# LIC_rack_BB-00.net
KiCad netlist of a schematic drawn in EAGLE
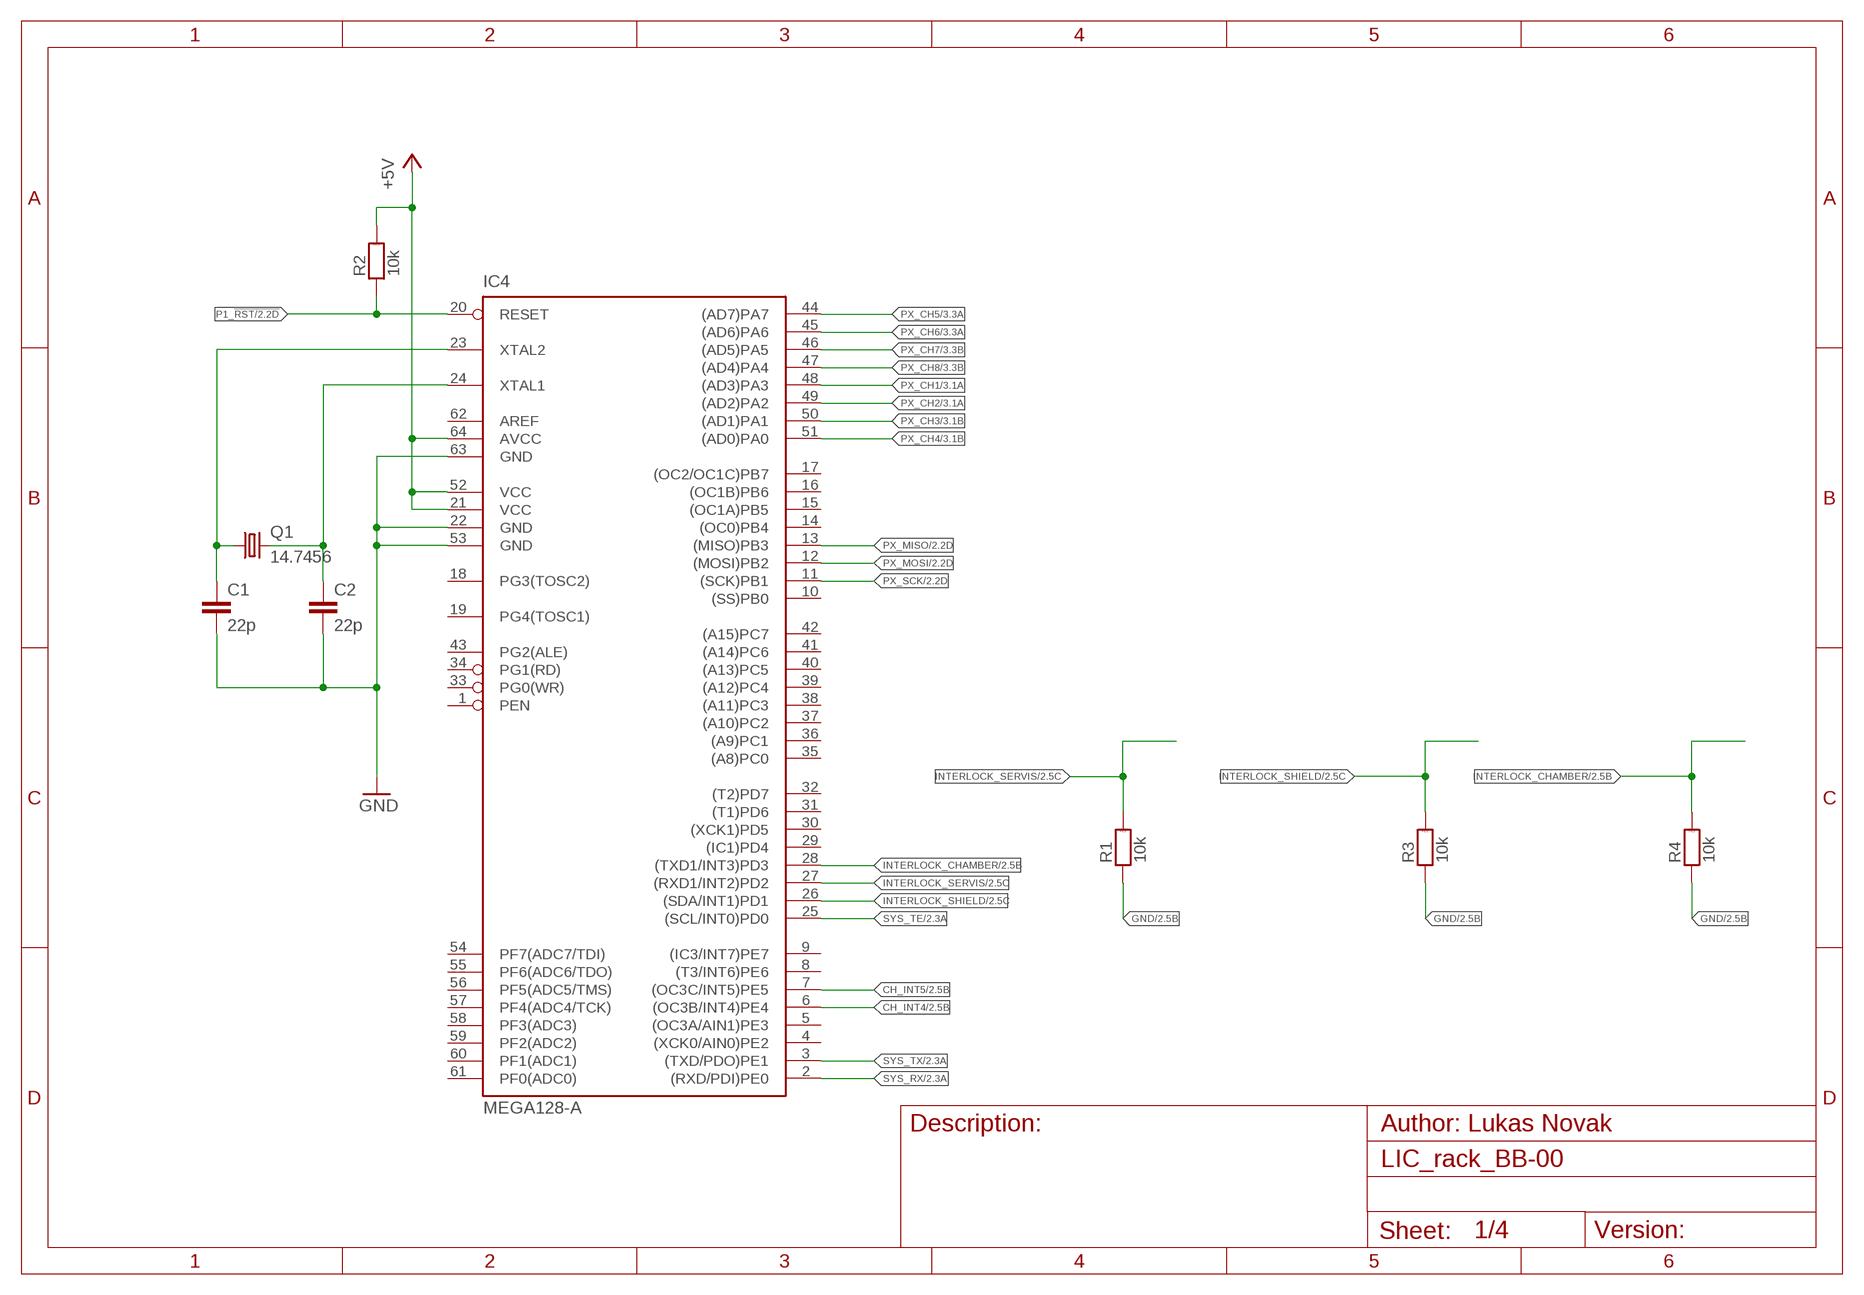
[diagram p0: schematic, sheet 1]
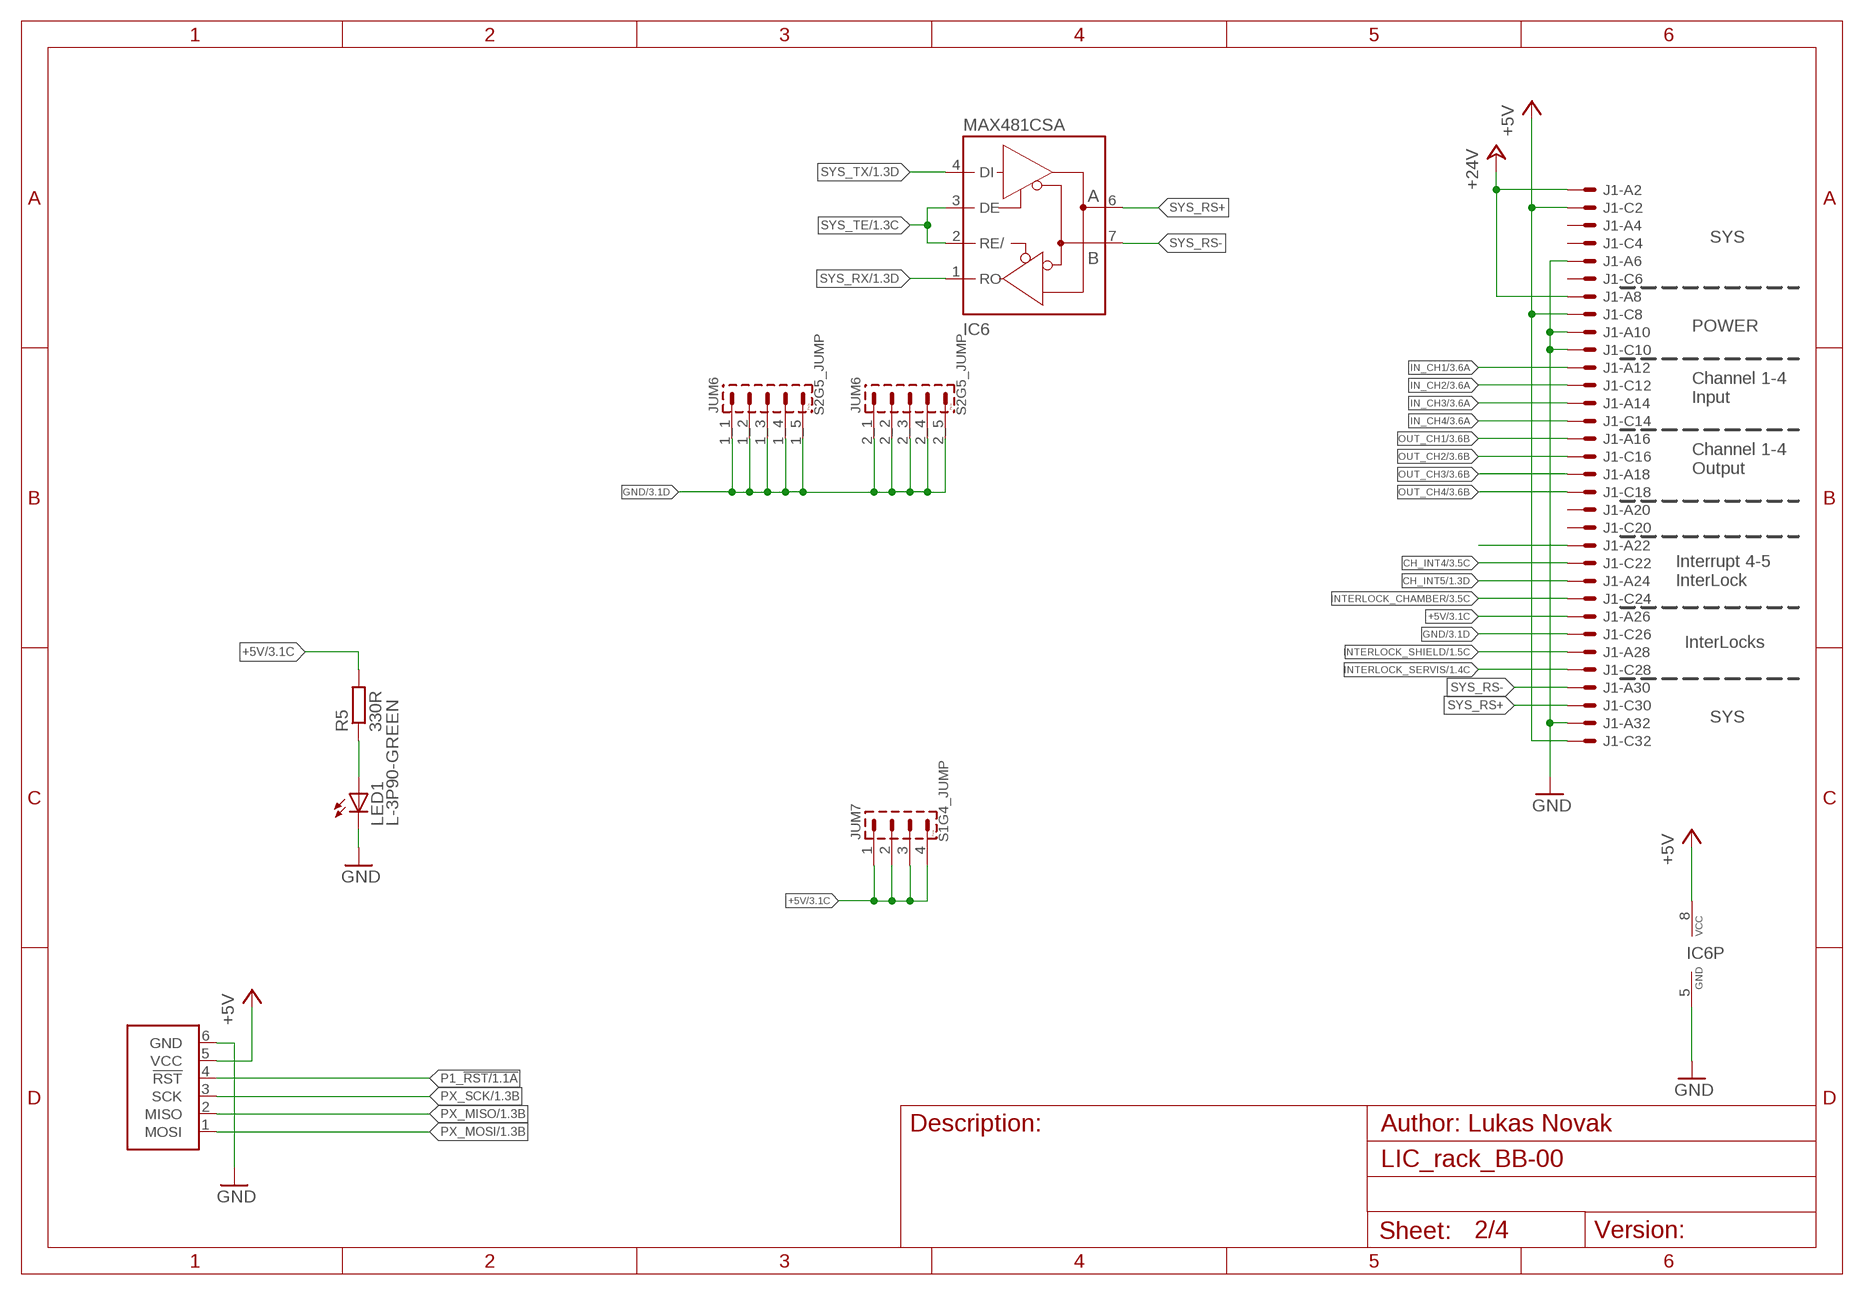
[diagram p1: schematic, sheet 2]
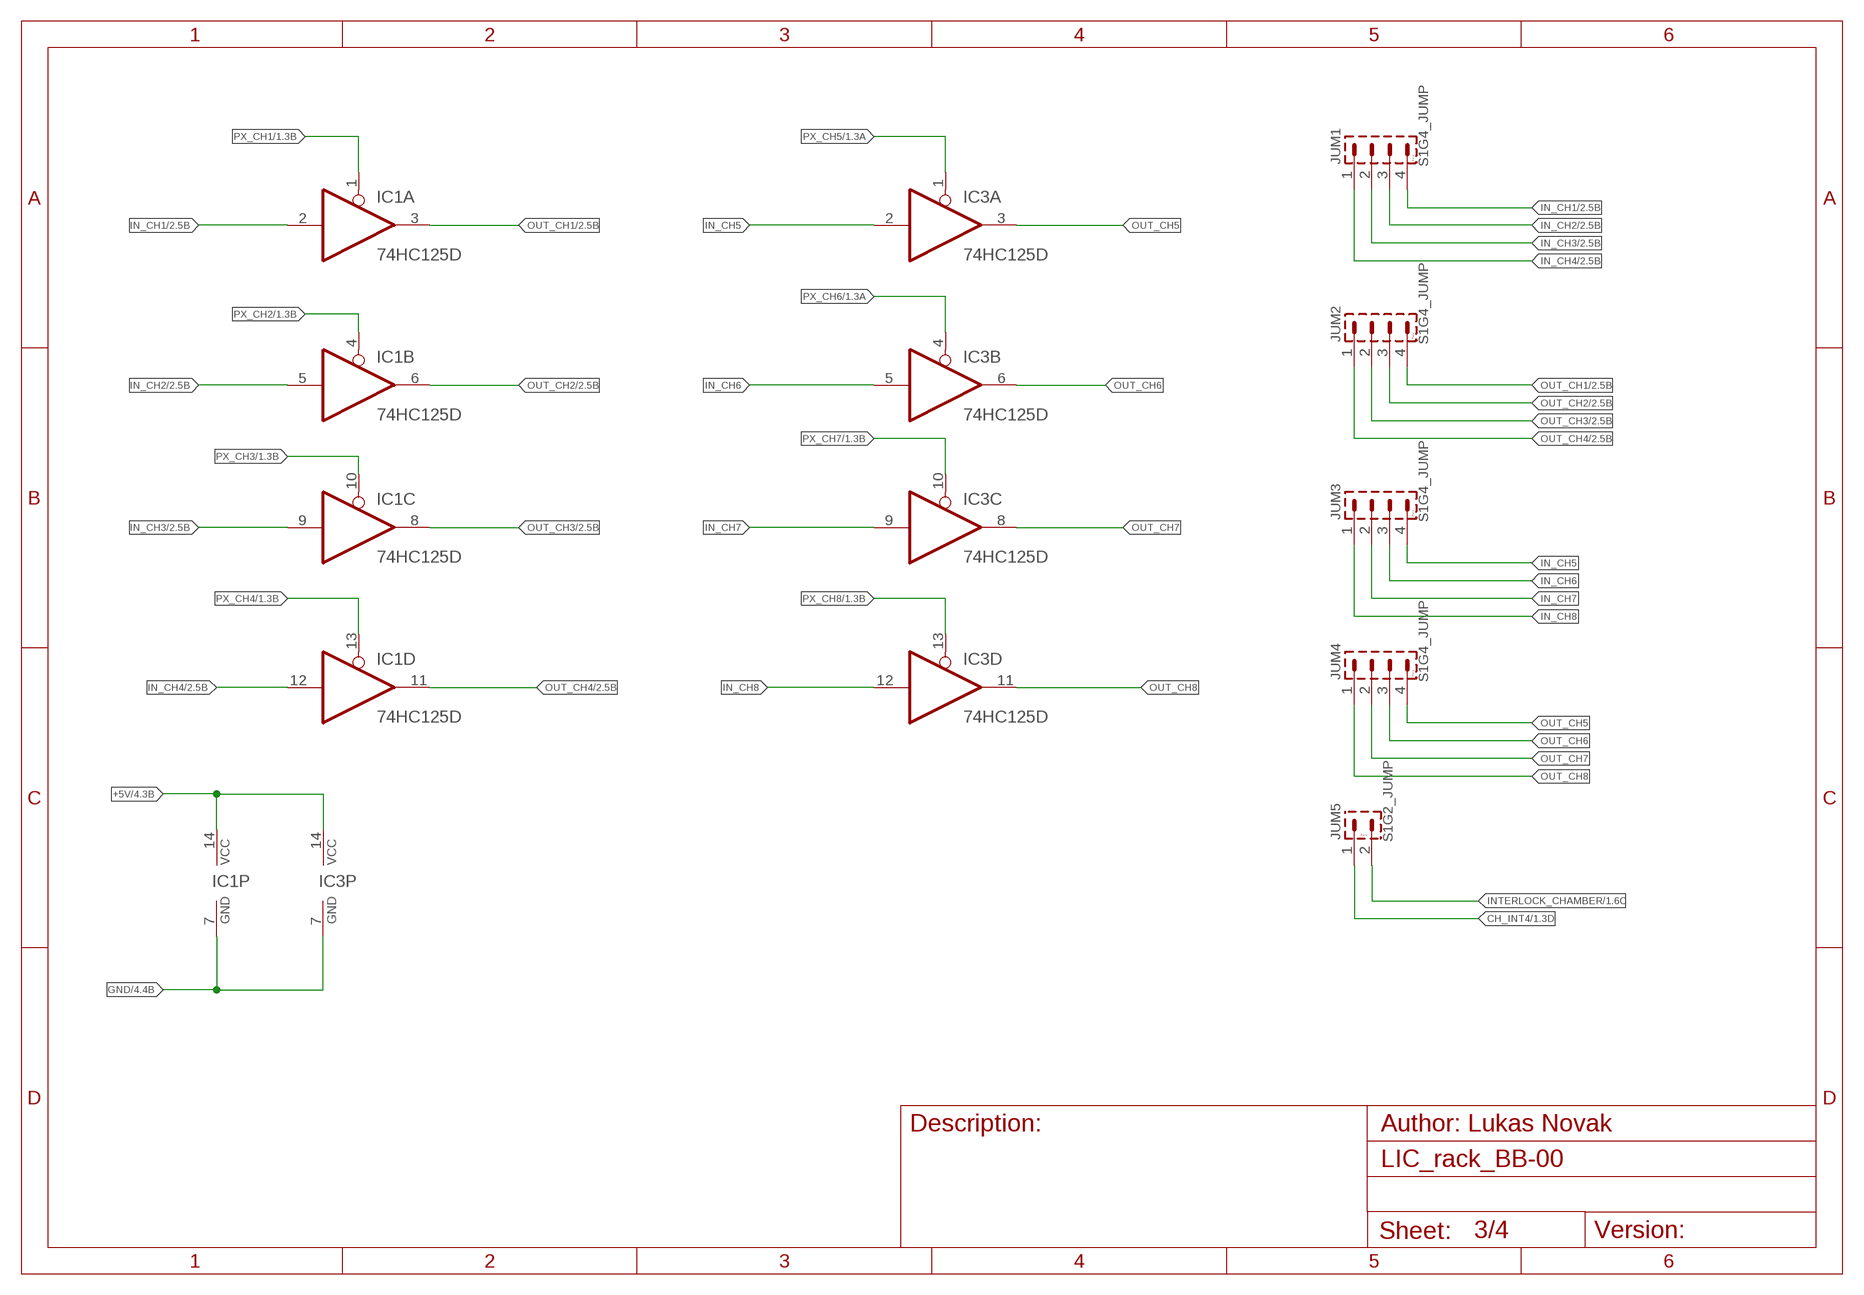
[diagram p2: schematic, sheet 3]
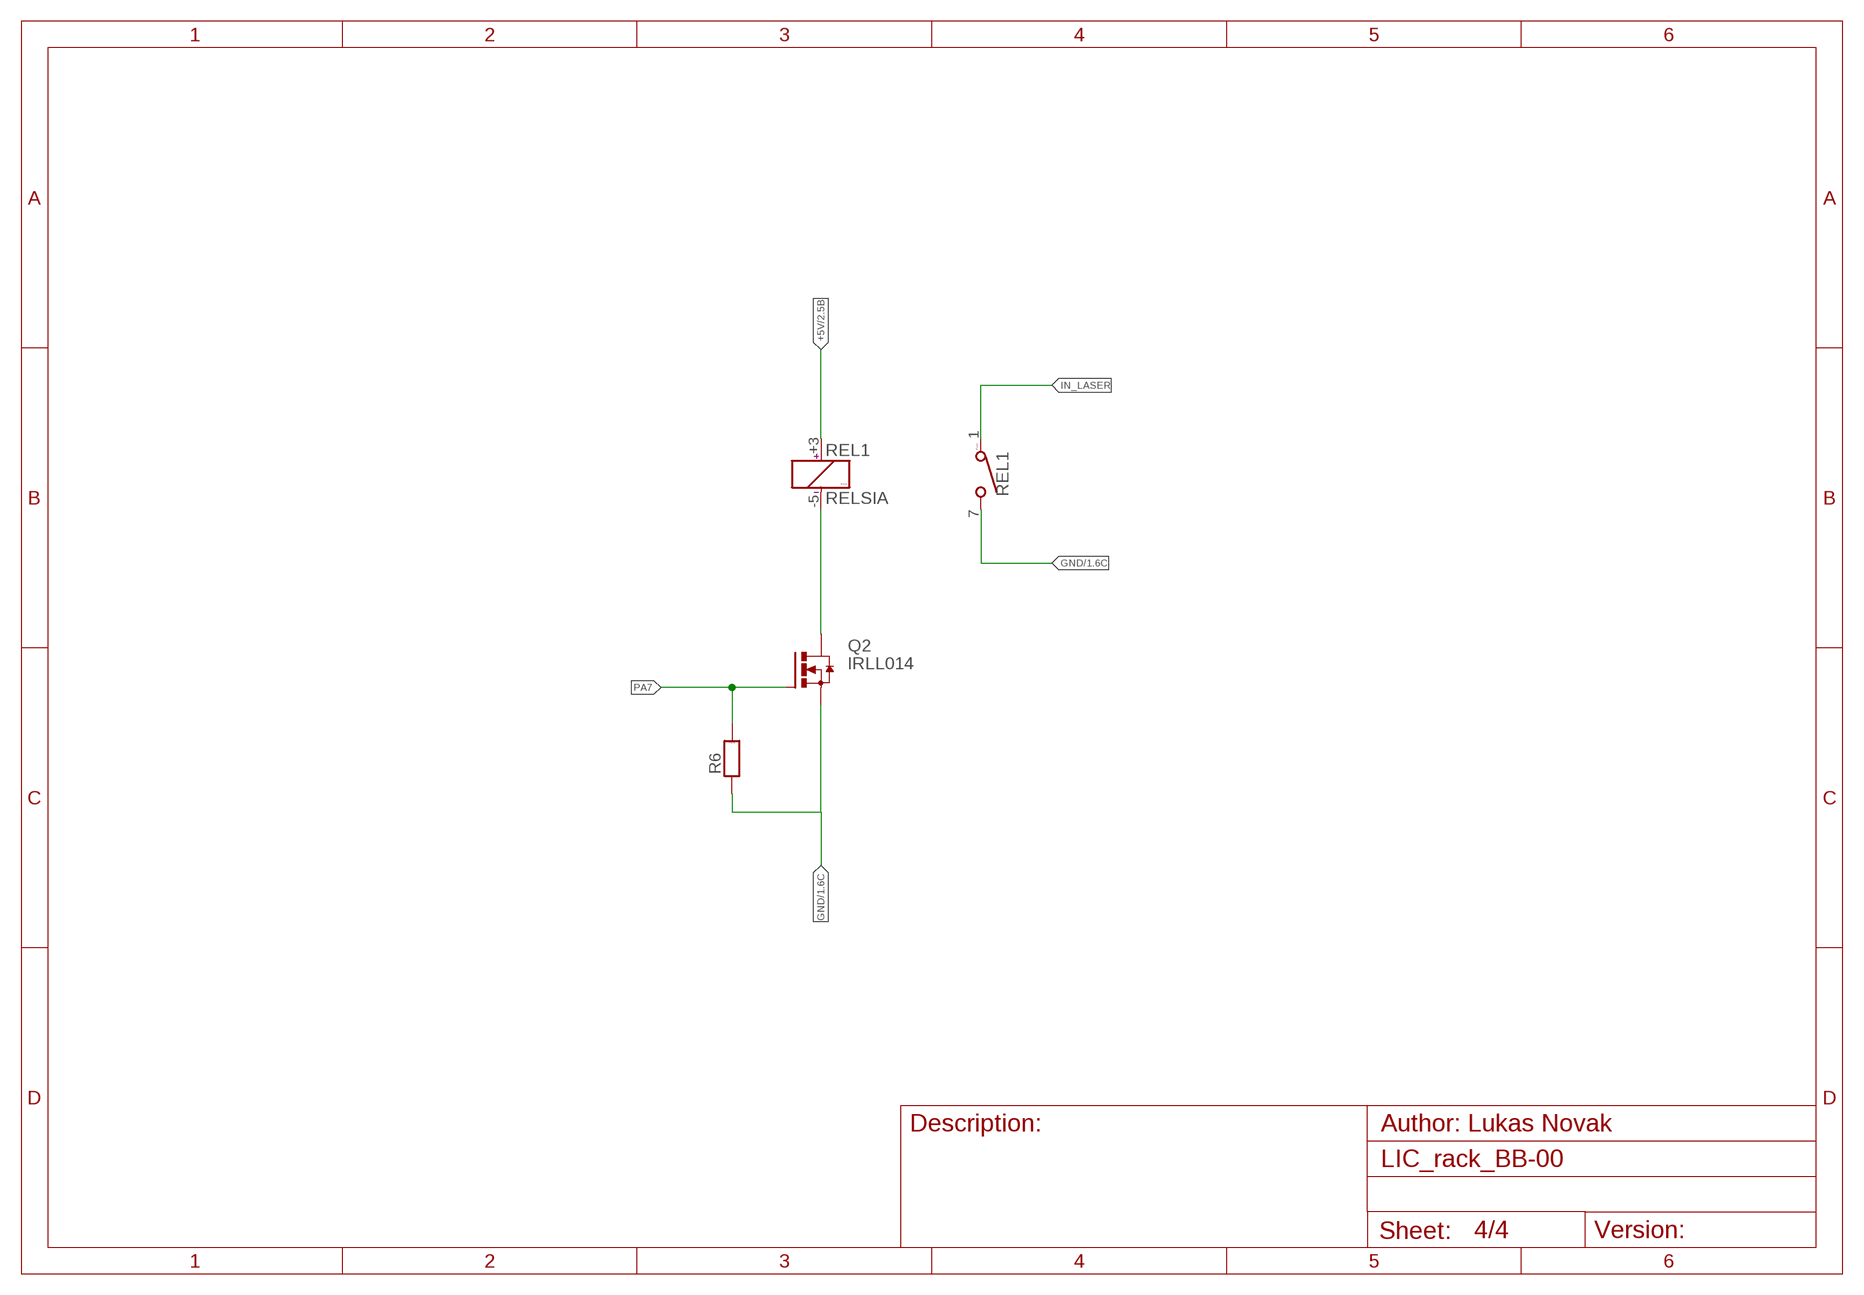
[diagram p3: schematic, sheet 4]

(export (version "E")
  (design (tool "Eeschema 10.0.6"))
  (components
    (comp (ref "C1")
      (value "22p")
      (footprint "eagle-import:C0805")
      (libsource (lib "eagle-import") (part "C-EUC0805"))
    )
    (comp (ref "C2")
      (value "22p")
      (footprint "eagle-import:C0805")
      (libsource (lib "eagle-import") (part "C-EUC0805"))
    )
    (comp (ref "IC4")
      (value "MEGA128-A")
      (footprint "eagle-import:TQFP64")
      (fields (field (name "MPN") "ATMEGA128-16AU"))
      (libsource (lib "eagle-import") (part "MEGA128-A"))
    )
    (comp (ref "Q1")
      (value "14.7456")
      (footprint "eagle-import:HC49U70")
      (libsource (lib "eagle-import") (part "XTAL"))
    )
    (comp (ref "R1")
      (value "10k")
      (footprint "eagle-import:1206")
      (libsource (lib "eagle-import") (part "R_1206"))
    )
    (comp (ref "R2")
      (value "10k")
      (footprint "eagle-import:1206")
      (libsource (lib "eagle-import") (part "R_1206"))
    )
    (comp (ref "R3")
      (value "10k")
      (footprint "eagle-import:1206")
      (libsource (lib "eagle-import") (part "R_1206"))
    )
    (comp (ref "R4")
      (value "10k")
      (footprint "eagle-import:1206")
      (libsource (lib "eagle-import") (part "R_1206"))
    )
    (comp (ref "IC1")
      (value "74HC125D")
      (footprint "eagle-import:SO14")
      (libsource (lib "eagle-import") (part "74125DHC"))
    )
    (comp (ref "IC3")
      (value "74HC125D")
      (footprint "eagle-import:SO14")
      (libsource (lib "eagle-import") (part "74125DHC"))
    )
    (comp (ref "JUM1")
      (value "S1G4_JUMP")
      (footprint "eagle-import:S1G4_JUM")
      (libsource (lib "eagle-import") (part "S1G4_JUMP"))
    )
    (comp (ref "JUM2")
      (value "S1G4_JUMP")
      (footprint "eagle-import:S1G4_JUM")
      (libsource (lib "eagle-import") (part "S1G4_JUMP"))
    )
    (comp (ref "JUM3")
      (value "S1G4_JUMP")
      (footprint "eagle-import:S1G4_JUM")
      (libsource (lib "eagle-import") (part "S1G4_JUMP"))
    )
    (comp (ref "JUM4")
      (value "S1G4_JUMP")
      (footprint "eagle-import:S1G4_JUM")
      (libsource (lib "eagle-import") (part "S1G4_JUMP"))
    )
    (comp (ref "JUM5")
      (value "S1G2_JUMP")
      (footprint "eagle-import:S1G2_JUM")
      (libsource (lib "eagle-import") (part "S1G2_JUMP"))
    )
    (comp (ref "IC6")
      (value "MAX481CSA")
      (footprint "eagle-import:SO08")
      (libsource (lib "eagle-import") (part "MAX481CSA"))
    )
    (comp (ref "J1")
      (value "VG32SP")
      (footprint "eagle-import:VG32P")
      (libsource (lib "eagle-import") (part "VG32SP"))
    )
    (comp (ref "JUM6")
      (value "S2G5_JUMP")
      (footprint "eagle-import:S2G5_JUM")
      (libsource (lib "eagle-import") (part "S2G5_JUMP"))
    )
    (comp (ref "JUM7")
      (value "S1G4_JUMP")
      (footprint "eagle-import:S1G4_JUM")
      (libsource (lib "eagle-import") (part "S1G4_JUMP"))
    )
    (comp (ref "LED1")
      (value "L-3P90-GREEN")
      (footprint "eagle-import:L-3P90")
      (libsource (lib "eagle-import") (part "L-3P90-GREEN"))
    )
    (comp (ref "R5")
      (value "330R")
      (footprint "eagle-import:R1206")
      (libsource (lib "eagle-import") (part "R-EU_R1206"))
    )
    (comp (ref "U1")
      (value "ATPROG-V")
      (footprint "eagle-import:6410-06")
      (libsource (lib "eagle-import") (part "ATPROG-V"))
    )
    (comp (ref "Q2")
      (value "IRLL014")
      (footprint "eagle-import:SOT223")
      (libsource (lib "eagle-import") (part "N-HEXFET-2D_?-SOT232"))
    )
    (comp (ref "R6")
      (value "R_1206")
      (footprint "eagle-import:1206")
      (libsource (lib "eagle-import") (part "R_1206"))
    )
    (comp (ref "REL1")
      (value "RELSIA")
      (footprint "eagle-import:RELSIA")
      (libsource (lib "eagle-import") (part "RELSIA??"))
    )
  )
  (nets
    (net (code "1") (name "+5V") (class "Default")
      (node (ref "IC1") (pin "14") (pinfunction "VCC_14") (pintype "power_in"))
      (node (ref "IC3") (pin "14") (pinfunction "VCC_14") (pintype "power_in"))
      (node (ref "IC4") (pin "21") (pinfunction "VCC_21") (pintype "power_in"))
      (node (ref "IC4") (pin "52") (pinfunction "VCC_52") (pintype "power_in"))
      (node (ref "IC4") (pin "64") (pinfunction "AVCC_64") (pintype "power_in"))
      (node (ref "IC6") (pin "8") (pinfunction "VCC_8") (pintype "power_in"))
      (node (ref "J1") (pin "A26") (pinfunction "MS_A26") (pintype "passive"))
      (node (ref "J1") (pin "C2") (pinfunction "MS_C2") (pintype "passive"))
      (node (ref "J1") (pin "C32") (pinfunction "MSV_C32") (pintype "passive"))
      (node (ref "J1") (pin "C8") (pinfunction "MS_C8") (pintype "passive"))
      (node (ref "JUM7") (pin "1") (pinfunction "1_1") (pintype "passive"))
      (node (ref "JUM7") (pin "2") (pinfunction "2_2") (pintype "passive"))
      (node (ref "JUM7") (pin "3") (pinfunction "3_3") (pintype "passive"))
      (node (ref "JUM7") (pin "4") (pinfunction "4_4") (pintype "passive"))
      (node (ref "R2") (pin "2") (pinfunction "2_2") (pintype "passive"))
      (node (ref "R5") (pin "2") (pinfunction "2_2") (pintype "passive"))
      (node (ref "REL1") (pin "+3") (pinfunction "C+_+3") (pintype "passive"))
      (node (ref "U1") (pin "5") (pinfunction "VCC_5") (pintype "power_in"))
    )
    (net (code "2") (name "+24V") (class "Default")
      (node (ref "J1") (pin "A2") (pinfunction "MS_A2") (pintype "passive"))
      (node (ref "J1") (pin "A8") (pinfunction "MS_A8") (pintype "passive"))
    )
    (net (code "3") (name "CH_INT4") (class "Default")
      (node (ref "IC4") (pin "6") (pinfunction "(OC3B/INT4)PE4_6") (pintype "bidirectional"))
      (node (ref "J1") (pin "C22") (pinfunction "MS_C22") (pintype "passive"))
      (node (ref "JUM5") (pin "1") (pinfunction "1_1") (pintype "passive"))
    )
    (net (code "4") (name "CH_INT5") (class "Default")
      (node (ref "IC4") (pin "7") (pinfunction "(OC3C/INT5)PE5_7") (pintype "bidirectional"))
      (node (ref "J1") (pin "A24") (pinfunction "MS_A24") (pintype "passive"))
    )
    (net (code "5") (name "GND") (class "Default")
      (node (ref "C1") (pin "2") (pinfunction "2_2") (pintype "passive"))
      (node (ref "C2") (pin "2") (pinfunction "2_2") (pintype "passive"))
      (node (ref "IC1") (pin "7") (pinfunction "GND_7") (pintype "power_in"))
      (node (ref "IC3") (pin "7") (pinfunction "GND_7") (pintype "power_in"))
      (node (ref "IC4") (pin "22") (pinfunction "GND_22") (pintype "power_in"))
      (node (ref "IC4") (pin "53") (pinfunction "GND_53") (pintype "power_in"))
      (node (ref "IC4") (pin "63") (pinfunction "GND_63") (pintype "power_in"))
      (node (ref "IC6") (pin "5") (pinfunction "GND_5") (pintype "power_in"))
      (node (ref "J1") (pin "A10") (pinfunction "MS_A10") (pintype "passive"))
      (node (ref "J1") (pin "A32") (pinfunction "MS_A32") (pintype "passive"))
      (node (ref "J1") (pin "A6") (pinfunction "MS_A6") (pintype "passive"))
      (node (ref "J1") (pin "C10") (pinfunction "MS_C10") (pintype "passive"))
      (node (ref "J1") (pin "C26") (pinfunction "MS_C26") (pintype "passive"))
      (node (ref "JUM6") (pin "1_1") (pinfunction "1_1_1") (pintype "passive"))
      (node (ref "JUM6") (pin "1_2") (pinfunction "2_1_2") (pintype "passive"))
      (node (ref "JUM6") (pin "1_3") (pinfunction "3_1_3") (pintype "passive"))
      (node (ref "JUM6") (pin "1_4") (pinfunction "4_1_4") (pintype "passive"))
      (node (ref "JUM6") (pin "1_5") (pinfunction "5_1_5") (pintype "passive"))
      (node (ref "JUM6") (pin "2_1") (pinfunction "1_2_1") (pintype "passive"))
      (node (ref "JUM6") (pin "2_2") (pinfunction "2_2_2") (pintype "passive"))
      (node (ref "JUM6") (pin "2_3") (pinfunction "3_2_3") (pintype "passive"))
      (node (ref "JUM6") (pin "2_4") (pinfunction "4_2_4") (pintype "passive"))
      (node (ref "JUM6") (pin "2_5") (pinfunction "5_2_5") (pintype "passive"))
      (node (ref "LED1") (pin "K") (pinfunction "C_K") (pintype "passive"))
      (node (ref "Q2") (pin "3") (pinfunction "S_3") (pintype "passive"))
      (node (ref "R1") (pin "1") (pinfunction "1_1") (pintype "passive"))
      (node (ref "R3") (pin "1") (pinfunction "1_1") (pintype "passive"))
      (node (ref "R4") (pin "1") (pinfunction "1_1") (pintype "passive"))
      (node (ref "R6") (pin "1") (pinfunction "1_1") (pintype "passive"))
      (node (ref "REL1") (pin "7") (pinfunction "2_7") (pintype "passive"))
      (node (ref "U1") (pin "6") (pinfunction "GND_6") (pintype "power_in"))
    )
    (net (code "6") (name "INTERLOCK_CHAMBER") (class "Default")
      (node (ref "IC4") (pin "28") (pinfunction "(TXD1/INT3)PD3_28") (pintype "bidirectional"))
      (node (ref "J1") (pin "C24") (pinfunction "MS_C24") (pintype "passive"))
      (node (ref "JUM5") (pin "2") (pinfunction "2_2") (pintype "passive"))
      (node (ref "R4") (pin "2") (pinfunction "2_2") (pintype "passive"))
    )
    (net (code "7") (name "INTERLOCK_SERVIS") (class "Default")
      (node (ref "IC4") (pin "27") (pinfunction "(RXD1/INT2)PD2_27") (pintype "bidirectional"))
      (node (ref "J1") (pin "C28") (pinfunction "MS_C28") (pintype "passive"))
      (node (ref "R1") (pin "2") (pinfunction "2_2") (pintype "passive"))
    )
    (net (code "8") (name "INTERLOCK_SHIELD") (class "Default")
      (node (ref "IC4") (pin "26") (pinfunction "(SDA/INT1)PD1_26") (pintype "bidirectional"))
      (node (ref "J1") (pin "A28") (pinfunction "MS_A28") (pintype "passive"))
      (node (ref "R3") (pin "2") (pinfunction "2_2") (pintype "passive"))
    )
    (net (code "9") (name "IN_CH1") (class "Default")
      (node (ref "IC1") (pin "2") (pinfunction "I_2") (pintype "input"))
      (node (ref "J1") (pin "A12") (pinfunction "MS_A12") (pintype "passive"))
      (node (ref "JUM1") (pin "4") (pinfunction "4_4") (pintype "passive"))
    )
    (net (code "10") (name "IN_CH2") (class "Default")
      (node (ref "IC1") (pin "5") (pinfunction "I_5") (pintype "input"))
      (node (ref "J1") (pin "C12") (pinfunction "MS_C12") (pintype "passive"))
      (node (ref "JUM1") (pin "3") (pinfunction "3_3") (pintype "passive"))
    )
    (net (code "11") (name "IN_CH3") (class "Default")
      (node (ref "IC1") (pin "9") (pinfunction "I_9") (pintype "input"))
      (node (ref "J1") (pin "A14") (pinfunction "MS_A14") (pintype "passive"))
      (node (ref "JUM1") (pin "2") (pinfunction "2_2") (pintype "passive"))
    )
    (net (code "12") (name "IN_CH4") (class "Default")
      (node (ref "IC1") (pin "12") (pinfunction "I_12") (pintype "input"))
      (node (ref "J1") (pin "C14") (pinfunction "MS_C14") (pintype "passive"))
      (node (ref "JUM1") (pin "1") (pinfunction "1_1") (pintype "passive"))
    )
    (net (code "13") (name "IN_CH5") (class "Default")
      (node (ref "IC3") (pin "2") (pinfunction "I_2") (pintype "input"))
      (node (ref "JUM3") (pin "4") (pinfunction "4_4") (pintype "passive"))
    )
    (net (code "14") (name "IN_CH6") (class "Default")
      (node (ref "IC3") (pin "5") (pinfunction "I_5") (pintype "input"))
      (node (ref "JUM3") (pin "3") (pinfunction "3_3") (pintype "passive"))
    )
    (net (code "15") (name "IN_CH7") (class "Default")
      (node (ref "IC3") (pin "9") (pinfunction "I_9") (pintype "input"))
      (node (ref "JUM3") (pin "2") (pinfunction "2_2") (pintype "passive"))
    )
    (net (code "16") (name "IN_CH8") (class "Default")
      (node (ref "IC3") (pin "12") (pinfunction "I_12") (pintype "input"))
      (node (ref "JUM3") (pin "1") (pinfunction "1_1") (pintype "passive"))
    )
    (net (code "17") (name "IN_LASER") (class "Default")
      (node (ref "REL1") (pin "1") (pinfunction "1_1") (pintype "passive"))
    )
    (net (code "18") (name "Net-(IC4-XTAL1)") (class "Default")
      (node (ref "C2") (pin "1") (pinfunction "1_1") (pintype "passive"))
      (node (ref "IC4") (pin "24") (pinfunction "XTAL1_24") (pintype "bidirectional"))
      (node (ref "Q1") (pin "2") (pinfunction "2_2") (pintype "passive"))
    )
    (net (code "19") (name "Net-(IC4-XTAL2)") (class "Default")
      (node (ref "C1") (pin "1") (pinfunction "1_1") (pintype "passive"))
      (node (ref "IC4") (pin "23") (pinfunction "XTAL2_23") (pintype "bidirectional"))
      (node (ref "Q1") (pin "1") (pinfunction "1_1") (pintype "passive"))
    )
    (net (code "20") (name "Net-(LED1-PadA)") (class "Default")
      (node (ref "LED1") (pin "A") (pinfunction "A_A") (pintype "passive"))
      (node (ref "R5") (pin "1") (pinfunction "1_1") (pintype "passive"))
    )
    (net (code "21") (name "Net-(REL1A-C-)") (class "Default")
      (node (ref "Q2") (pin "2") (pinfunction "D_2") (pintype "passive"))
      (node (ref "Q2") (pin "4") (pinfunction "D_4") (pintype "passive"))
      (node (ref "REL1") (pin "-5") (pinfunction "C-_-5") (pintype "passive"))
    )
    (net (code "22") (name "OUT_CH1") (class "Default")
      (node (ref "IC1") (pin "3") (pinfunction "O_3") (pintype "tri_state"))
      (node (ref "J1") (pin "A16") (pinfunction "MS_A16") (pintype "passive"))
      (node (ref "JUM2") (pin "4") (pinfunction "4_4") (pintype "passive"))
    )
    (net (code "23") (name "OUT_CH2") (class "Default")
      (node (ref "IC1") (pin "6") (pinfunction "O_6") (pintype "tri_state"))
      (node (ref "J1") (pin "C16") (pinfunction "MS_C16") (pintype "passive"))
      (node (ref "JUM2") (pin "3") (pinfunction "3_3") (pintype "passive"))
    )
    (net (code "24") (name "OUT_CH3") (class "Default")
      (node (ref "IC1") (pin "8") (pinfunction "O_8") (pintype "tri_state"))
      (node (ref "J1") (pin "A18") (pinfunction "MS_A18") (pintype "passive"))
      (node (ref "JUM2") (pin "2") (pinfunction "2_2") (pintype "passive"))
    )
    (net (code "25") (name "OUT_CH4") (class "Default")
      (node (ref "IC1") (pin "11") (pinfunction "O_11") (pintype "tri_state"))
      (node (ref "J1") (pin "C18") (pinfunction "MS_C18") (pintype "passive"))
      (node (ref "JUM2") (pin "1") (pinfunction "1_1") (pintype "passive"))
    )
    (net (code "26") (name "OUT_CH5") (class "Default")
      (node (ref "IC3") (pin "3") (pinfunction "O_3") (pintype "tri_state"))
      (node (ref "JUM4") (pin "4") (pinfunction "4_4") (pintype "passive"))
    )
    (net (code "27") (name "OUT_CH6") (class "Default")
      (node (ref "IC3") (pin "6") (pinfunction "O_6") (pintype "tri_state"))
      (node (ref "JUM4") (pin "3") (pinfunction "3_3") (pintype "passive"))
    )
    (net (code "28") (name "OUT_CH7") (class "Default")
      (node (ref "IC3") (pin "8") (pinfunction "O_8") (pintype "tri_state"))
      (node (ref "JUM4") (pin "2") (pinfunction "2_2") (pintype "passive"))
    )
    (net (code "29") (name "OUT_CH8") (class "Default")
      (node (ref "IC3") (pin "11") (pinfunction "O_11") (pintype "tri_state"))
      (node (ref "JUM4") (pin "1") (pinfunction "1_1") (pintype "passive"))
    )
    (net (code "30") (name "P1_~{RST}") (class "Default")
      (node (ref "IC4") (pin "20") (pinfunction "RESET_20") (pintype "input"))
      (node (ref "R2") (pin "1") (pinfunction "1_1") (pintype "passive"))
      (node (ref "U1") (pin "4") (pinfunction "~{RST}_4") (pintype "input"))
    )
    (net (code "31") (name "PA7") (class "Default")
      (node (ref "Q2") (pin "1") (pinfunction "G_1") (pintype "passive"))
      (node (ref "R6") (pin "2") (pinfunction "2_2") (pintype "passive"))
    )
    (net (code "32") (name "PX_CH1") (class "Default")
      (node (ref "IC1") (pin "1") (pinfunction "OE_1") (pintype "input"))
      (node (ref "IC4") (pin "48") (pinfunction "(AD3)PA3_48") (pintype "bidirectional"))
    )
    (net (code "33") (name "PX_CH2") (class "Default")
      (node (ref "IC1") (pin "4") (pinfunction "OE_4") (pintype "input"))
      (node (ref "IC4") (pin "49") (pinfunction "(AD2)PA2_49") (pintype "bidirectional"))
    )
    (net (code "34") (name "PX_CH3") (class "Default")
      (node (ref "IC1") (pin "10") (pinfunction "OE_10") (pintype "input"))
      (node (ref "IC4") (pin "50") (pinfunction "(AD1)PA1_50") (pintype "bidirectional"))
    )
    (net (code "35") (name "PX_CH4") (class "Default")
      (node (ref "IC1") (pin "13") (pinfunction "OE_13") (pintype "input"))
      (node (ref "IC4") (pin "51") (pinfunction "(AD0)PA0_51") (pintype "bidirectional"))
    )
    (net (code "36") (name "PX_CH5") (class "Default")
      (node (ref "IC3") (pin "1") (pinfunction "OE_1") (pintype "input"))
      (node (ref "IC4") (pin "44") (pinfunction "(AD7)PA7_44") (pintype "bidirectional"))
      (node (ref "J1") (pin "A22") (pinfunction "MS_A22") (pintype "passive"))
    )
    (net (code "37") (name "PX_CH6") (class "Default")
      (node (ref "IC3") (pin "4") (pinfunction "OE_4") (pintype "input"))
      (node (ref "IC4") (pin "45") (pinfunction "(AD6)PA6_45") (pintype "bidirectional"))
    )
    (net (code "38") (name "PX_CH7") (class "Default")
      (node (ref "IC3") (pin "10") (pinfunction "OE_10") (pintype "input"))
      (node (ref "IC4") (pin "46") (pinfunction "(AD5)PA5_46") (pintype "bidirectional"))
    )
    (net (code "39") (name "PX_CH8") (class "Default")
      (node (ref "IC3") (pin "13") (pinfunction "OE_13") (pintype "input"))
      (node (ref "IC4") (pin "47") (pinfunction "(AD4)PA4_47") (pintype "bidirectional"))
    )
    (net (code "40") (name "PX_MISO") (class "Default")
      (node (ref "IC4") (pin "13") (pinfunction "(MISO)PB3_13") (pintype "bidirectional"))
      (node (ref "U1") (pin "2") (pinfunction "MISO_2") (pintype "input"))
    )
    (net (code "41") (name "PX_MOSI") (class "Default")
      (node (ref "IC4") (pin "12") (pinfunction "(MOSI)PB2_12") (pintype "bidirectional"))
      (node (ref "U1") (pin "1") (pinfunction "MOSI_1") (pintype "output"))
    )
    (net (code "42") (name "PX_SCK") (class "Default")
      (node (ref "IC4") (pin "11") (pinfunction "(SCK)PB1_11") (pintype "bidirectional"))
      (node (ref "U1") (pin "3") (pinfunction "SCK_3") (pintype "input"))
    )
    (net (code "43") (name "SYS_RS+") (class "Default")
      (node (ref "IC6") (pin "6") (pinfunction "A_6") (pintype "passive"))
      (node (ref "J1") (pin "C30") (pinfunction "MS_C30") (pintype "passive"))
    )
    (net (code "44") (name "SYS_RS-") (class "Default")
      (node (ref "IC6") (pin "7") (pinfunction "B_7") (pintype "passive"))
      (node (ref "J1") (pin "A30") (pinfunction "MS_A30") (pintype "passive"))
    )
    (net (code "45") (name "SYS_RX") (class "Default")
      (node (ref "IC4") (pin "2") (pinfunction "(RXD/PDI)PE0_2") (pintype "bidirectional"))
      (node (ref "IC6") (pin "1") (pinfunction "RO_1") (pintype "output"))
    )
    (net (code "46") (name "SYS_TE") (class "Default")
      (node (ref "IC4") (pin "25") (pinfunction "(SCL/INT0)PD0_25") (pintype "bidirectional"))
      (node (ref "IC6") (pin "2") (pinfunction "RE/_2") (pintype "input"))
      (node (ref "IC6") (pin "3") (pinfunction "DE_3") (pintype "input"))
    )
    (net (code "47") (name "SYS_TX") (class "Default")
      (node (ref "IC4") (pin "3") (pinfunction "(TXD/PDO)PE1_3") (pintype "bidirectional"))
      (node (ref "IC6") (pin "4") (pinfunction "DI_4") (pintype "input"))
    )
    (net (code "48") (name "unconnected-(IC4-(A8)PC0-Pad35)") (class "Default")
      (node (ref "IC4") (pin "35") (pinfunction "(A8)PC0_35") (pintype "output"))
    )
    (net (code "49") (name "unconnected-(IC4-(A9)PC1-Pad36)") (class "Default")
      (node (ref "IC4") (pin "36") (pinfunction "(A9)PC1_36") (pintype "output"))
    )
    (net (code "50") (name "unconnected-(IC4-(A10)PC2-Pad37)") (class "Default")
      (node (ref "IC4") (pin "37") (pinfunction "(A10)PC2_37") (pintype "output"))
    )
    (net (code "51") (name "unconnected-(IC4-(A11)PC3-Pad38)") (class "Default")
      (node (ref "IC4") (pin "38") (pinfunction "(A11)PC3_38") (pintype "output"))
    )
    (net (code "52") (name "unconnected-(IC4-(A12)PC4-Pad39)") (class "Default")
      (node (ref "IC4") (pin "39") (pinfunction "(A12)PC4_39") (pintype "output"))
    )
    (net (code "53") (name "unconnected-(IC4-(A13)PC5-Pad40)") (class "Default")
      (node (ref "IC4") (pin "40") (pinfunction "(A13)PC5_40") (pintype "output"))
    )
    (net (code "54") (name "unconnected-(IC4-(A14)PC6-Pad41)") (class "Default")
      (node (ref "IC4") (pin "41") (pinfunction "(A14)PC6_41") (pintype "output"))
    )
    (net (code "55") (name "unconnected-(IC4-(A15)PC7-Pad42)") (class "Default")
      (node (ref "IC4") (pin "42") (pinfunction "(A15)PC7_42") (pintype "output"))
    )
    (net (code "56") (name "unconnected-(IC4-(IC1)PD4-Pad29)") (class "Default")
      (node (ref "IC4") (pin "29") (pinfunction "(IC1)PD4_29") (pintype "bidirectional"))
    )
    (net (code "57") (name "unconnected-(IC4-(IC3{slash}INT7)PE7-Pad9)") (class "Default")
      (node (ref "IC4") (pin "9") (pinfunction "(IC3/INT7)PE7_9") (pintype "bidirectional"))
    )
    (net (code "58") (name "unconnected-(IC4-(OC0)PB4-Pad14)") (class "Default")
      (node (ref "IC4") (pin "14") (pinfunction "(OC0)PB4_14") (pintype "bidirectional"))
    )
    (net (code "59") (name "unconnected-(IC4-(OC1A)PB5-Pad15)") (class "Default")
      (node (ref "IC4") (pin "15") (pinfunction "(OC1A)PB5_15") (pintype "bidirectional"))
    )
    (net (code "60") (name "unconnected-(IC4-(OC1B)PB6-Pad16)") (class "Default")
      (node (ref "IC4") (pin "16") (pinfunction "(OC1B)PB6_16") (pintype "bidirectional"))
    )
    (net (code "61") (name "unconnected-(IC4-(OC2{slash}OC1C)PB7-Pad17)") (class "Default")
      (node (ref "IC4") (pin "17") (pinfunction "(OC2/OC1C)PB7_17") (pintype "bidirectional"))
    )
    (net (code "62") (name "unconnected-(IC4-(OC3A{slash}AIN1)PE3-Pad5)") (class "Default")
      (node (ref "IC4") (pin "5") (pinfunction "(OC3A/AIN1)PE3_5") (pintype "bidirectional"))
    )
    (net (code "63") (name "unconnected-(IC4-(SS)PB0-Pad10)") (class "Default")
      (node (ref "IC4") (pin "10") (pinfunction "(SS)PB0_10") (pintype "bidirectional"))
    )
    (net (code "64") (name "unconnected-(IC4-(T1)PD6-Pad31)") (class "Default")
      (node (ref "IC4") (pin "31") (pinfunction "(T1)PD6_31") (pintype "bidirectional"))
    )
    (net (code "65") (name "unconnected-(IC4-(T2)PD7-Pad32)") (class "Default")
      (node (ref "IC4") (pin "32") (pinfunction "(T2)PD7_32") (pintype "bidirectional"))
    )
    (net (code "66") (name "unconnected-(IC4-(T3{slash}INT6)PE6-Pad8)") (class "Default")
      (node (ref "IC4") (pin "8") (pinfunction "(T3/INT6)PE6_8") (pintype "bidirectional"))
    )
    (net (code "67") (name "unconnected-(IC4-(XCK0{slash}AIN0)PE2-Pad4)") (class "Default")
      (node (ref "IC4") (pin "4") (pinfunction "(XCK0/AIN0)PE2_4") (pintype "bidirectional"))
    )
    (net (code "68") (name "unconnected-(IC4-(XCK1)PD5-Pad30)") (class "Default")
      (node (ref "IC4") (pin "30") (pinfunction "(XCK1)PD5_30") (pintype "bidirectional"))
    )
    (net (code "69") (name "unconnected-(IC4-AREF-Pad62)") (class "Default")
      (node (ref "IC4") (pin "62") (pinfunction "AREF_62") (pintype "passive"))
    )
    (net (code "70") (name "unconnected-(IC4-PEN-Pad1)") (class "Default")
      (node (ref "IC4") (pin "1") (pinfunction "PEN_1") (pintype "input"))
    )
    (net (code "71") (name "unconnected-(IC4-PF0(ADC0)-Pad61)") (class "Default")
      (node (ref "IC4") (pin "61") (pinfunction "PF0(ADC0)_61") (pintype "input"))
    )
    (net (code "72") (name "unconnected-(IC4-PF1(ADC1)-Pad60)") (class "Default")
      (node (ref "IC4") (pin "60") (pinfunction "PF1(ADC1)_60") (pintype "input"))
    )
    (net (code "73") (name "unconnected-(IC4-PF2(ADC2)-Pad59)") (class "Default")
      (node (ref "IC4") (pin "59") (pinfunction "PF2(ADC2)_59") (pintype "input"))
    )
    (net (code "74") (name "unconnected-(IC4-PF3(ADC3)-Pad58)") (class "Default")
      (node (ref "IC4") (pin "58") (pinfunction "PF3(ADC3)_58") (pintype "input"))
    )
    (net (code "75") (name "unconnected-(IC4-PF4(ADC4{slash}TCK)-Pad57)") (class "Default")
      (node (ref "IC4") (pin "57") (pinfunction "PF4(ADC4/TCK)_57") (pintype "input"))
    )
    (net (code "76") (name "unconnected-(IC4-PF5(ADC5{slash}TMS)-Pad56)") (class "Default")
      (node (ref "IC4") (pin "56") (pinfunction "PF5(ADC5/TMS)_56") (pintype "input"))
    )
    (net (code "77") (name "unconnected-(IC4-PF6(ADC6{slash}TDO)-Pad55)") (class "Default")
      (node (ref "IC4") (pin "55") (pinfunction "PF6(ADC6/TDO)_55") (pintype "input"))
    )
    (net (code "78") (name "unconnected-(IC4-PF7(ADC7{slash}TDI)-Pad54)") (class "Default")
      (node (ref "IC4") (pin "54") (pinfunction "PF7(ADC7/TDI)_54") (pintype "input"))
    )
    (net (code "79") (name "unconnected-(IC4-PG0(WR)-Pad33)") (class "Default")
      (node (ref "IC4") (pin "33") (pinfunction "PG0(WR)_33") (pintype "bidirectional"))
    )
    (net (code "80") (name "unconnected-(IC4-PG1(RD)-Pad34)") (class "Default")
      (node (ref "IC4") (pin "34") (pinfunction "PG1(RD)_34") (pintype "bidirectional"))
    )
    (net (code "81") (name "unconnected-(IC4-PG2(ALE)-Pad43)") (class "Default")
      (node (ref "IC4") (pin "43") (pinfunction "PG2(ALE)_43") (pintype "bidirectional"))
    )
    (net (code "82") (name "unconnected-(IC4-PG3(TOSC2)-Pad18)") (class "Default")
      (node (ref "IC4") (pin "18") (pinfunction "PG3(TOSC2)_18") (pintype "bidirectional"))
    )
    (net (code "83") (name "unconnected-(IC4-PG4(TOSC1)-Pad19)") (class "Default")
      (node (ref "IC4") (pin "19") (pinfunction "PG4(TOSC1)_19") (pintype "bidirectional"))
    )
    (net (code "84") (name "unconnected-(J1AD-MS-PadC4)") (class "Default")
      (node (ref "J1") (pin "C4") (pinfunction "MS_C4") (pintype "passive"))
    )
    (net (code "85") (name "unconnected-(J1AE-MS-PadC6)") (class "Default")
      (node (ref "J1") (pin "C6") (pinfunction "MS_C6") (pintype "passive"))
    )
    (net (code "86") (name "unconnected-(J1G-MS-PadA20)") (class "Default")
      (node (ref "J1") (pin "A20") (pinfunction "MS_A20") (pintype "passive"))
    )
    (net (code "87") (name "unconnected-(J1N-MS-PadA4)") (class "Default")
      (node (ref "J1") (pin "A4") (pinfunction "MS_A4") (pintype "passive"))
    )
    (net (code "88") (name "unconnected-(J1W-MS-PadC20)") (class "Default")
      (node (ref "J1") (pin "C20") (pinfunction "MS_C20") (pintype "passive"))
    )
  )
)
